# EBN_Storage_V01.net
KiCad netlist of a schematic drawn in EAGLE
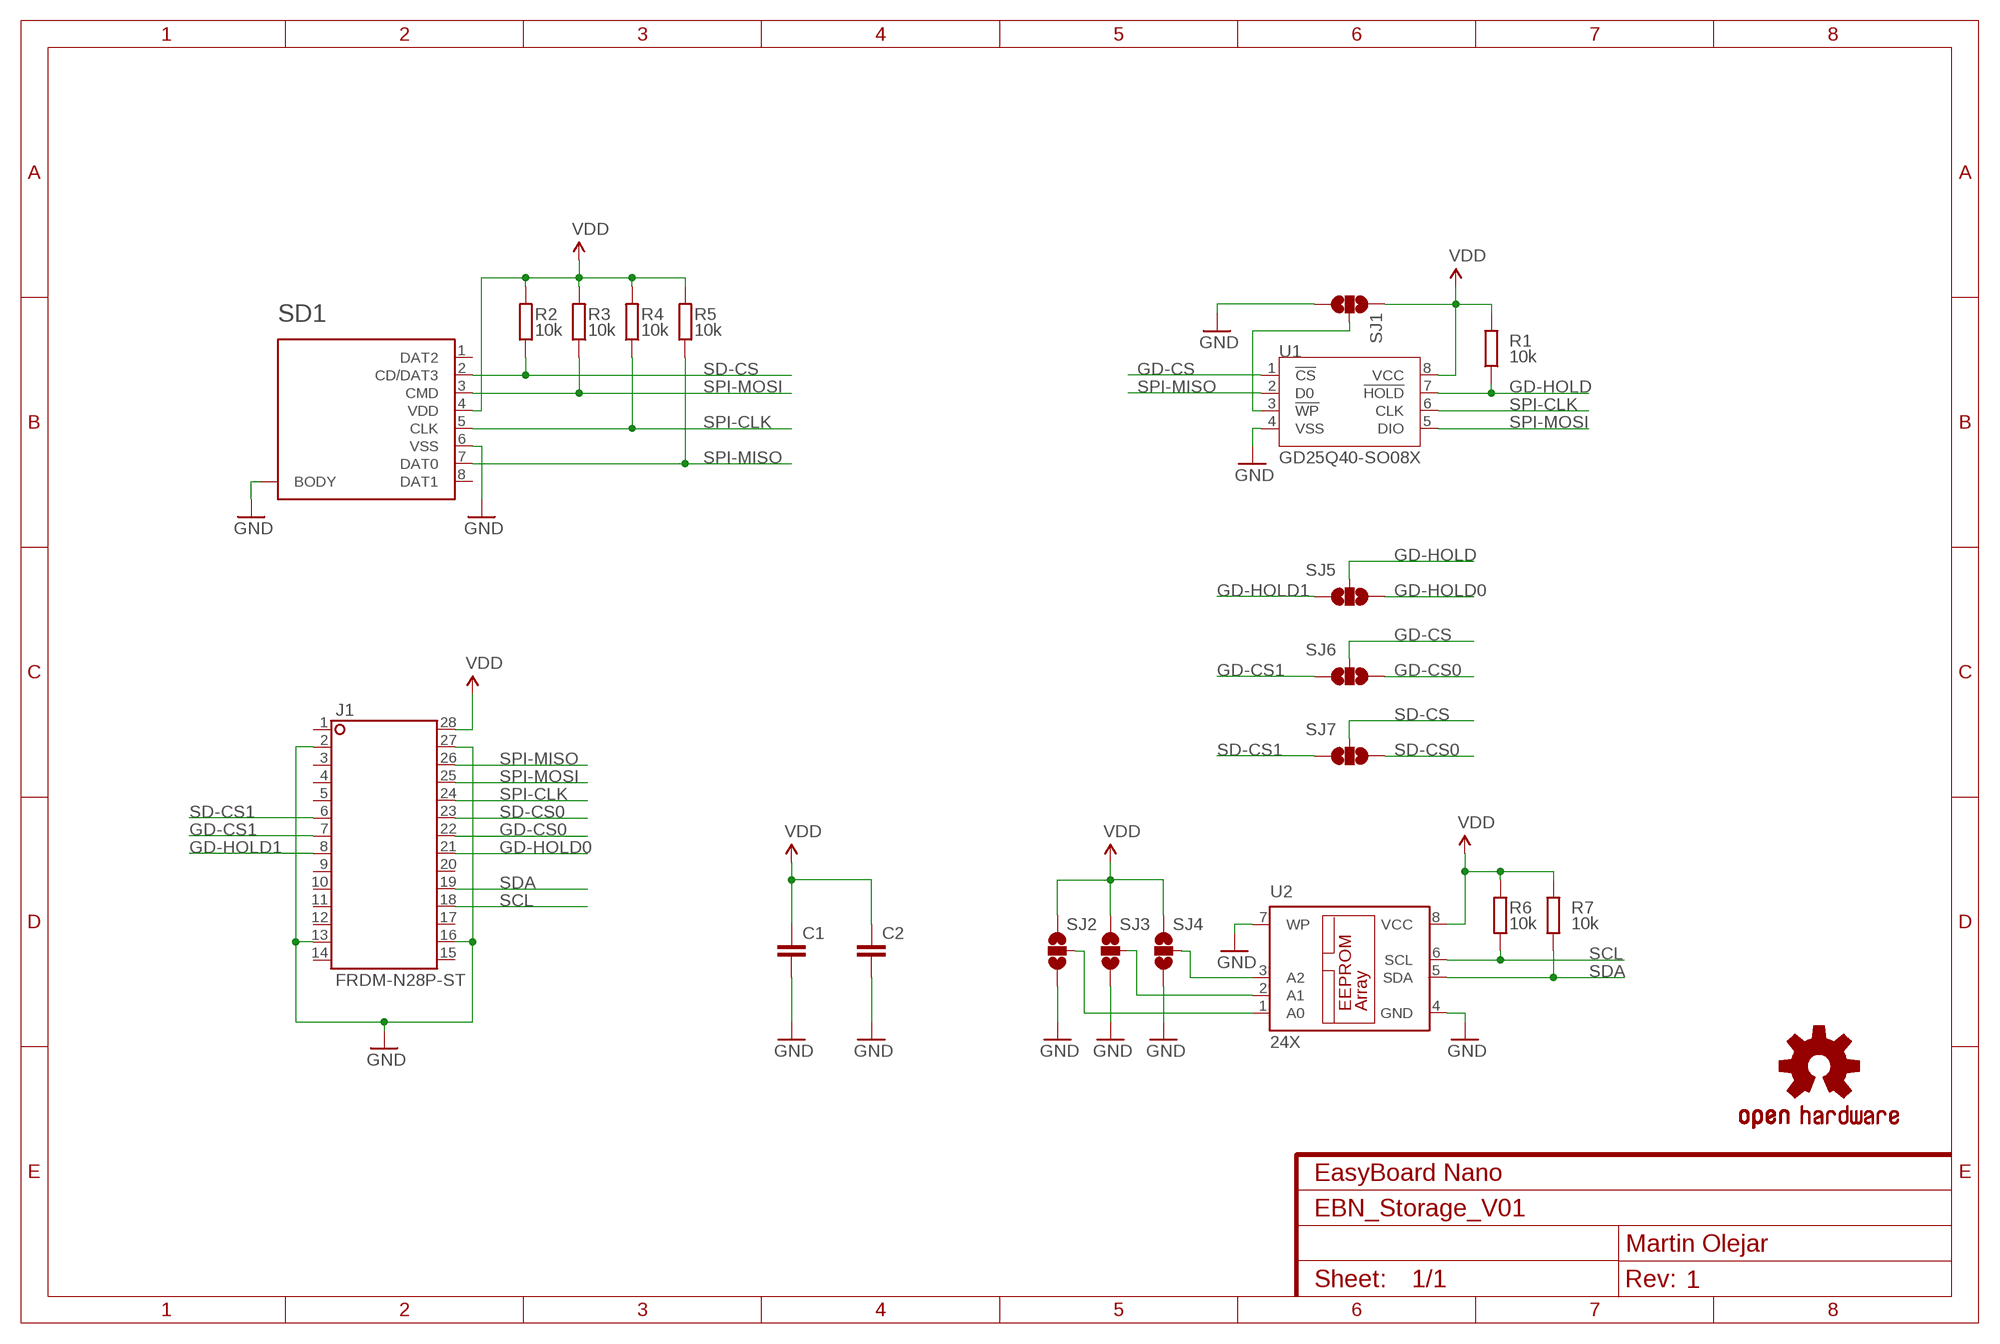
[diagram p0: schematic, sheet 1]

(export (version "E")
  (design (tool "Eeschema 10.0.6"))
  (components
    (comp (ref "C1")
      (value "C-EUC0402")
      (footprint "eagle-import:C0402")
      (libsource (lib "eagle-import") (part "C-EUC0402"))
    )
    (comp (ref "C2")
      (value "C-EUC0603")
      (footprint "eagle-import:C0603")
      (libsource (lib "eagle-import") (part "C-EUC0603"))
    )
    (comp (ref "J1")
      (value "FRDM-N28P-ST")
      (footprint "eagle-import:FRDM-N28P-SHIELD")
      (libsource (lib "eagle-import") (part "FRDM-N28P-ST"))
    )
    (comp (ref "LOGO1")
      (value "OSHW-LOGOM")
      (footprint "eagle-import:OSHW-LOGO-M")
      (libsource (lib "eagle-import") (part "OSHW-LOGOM"))
    )
    (comp (ref "R1")
      (value "10k")
      (footprint "eagle-import:R0603")
      (libsource (lib "eagle-import") (part "R-EUR0603"))
    )
    (comp (ref "R2")
      (value "10k")
      (footprint "eagle-import:R0402")
      (libsource (lib "eagle-import") (part "R-EUR0402"))
    )
    (comp (ref "R3")
      (value "10k")
      (footprint "eagle-import:R0402")
      (libsource (lib "eagle-import") (part "R-EUR0402"))
    )
    (comp (ref "R4")
      (value "10k")
      (footprint "eagle-import:R0402")
      (libsource (lib "eagle-import") (part "R-EUR0402"))
    )
    (comp (ref "R5")
      (value "10k")
      (footprint "eagle-import:R0402")
      (libsource (lib "eagle-import") (part "R-EUR0402"))
    )
    (comp (ref "R6")
      (value "10k")
      (footprint "eagle-import:R0603")
      (libsource (lib "eagle-import") (part "R-EUR0603"))
    )
    (comp (ref "R7")
      (value "10k")
      (footprint "eagle-import:R0603")
      (libsource (lib "eagle-import") (part "R-EUR0603"))
    )
    (comp (ref "SD1")
      (value "SDCARD")
      (footprint "eagle-import:MICRO-SD-01")
      (libsource (lib "eagle-import") (part "SDCARD"))
    )
    (comp (ref "SJ1")
      (value "SJ2W-S")
      (footprint "eagle-import:JUMPER-SMD-S2X")
      (libsource (lib "eagle-import") (part "SJ2W-S"))
    )
    (comp (ref "SJ2")
      (value "SJ2W-S")
      (footprint "eagle-import:JUMPER-SMD-S2X")
      (libsource (lib "eagle-import") (part "SJ2W-S"))
    )
    (comp (ref "SJ3")
      (value "SJ2W-S")
      (footprint "eagle-import:JUMPER-SMD-S2X")
      (libsource (lib "eagle-import") (part "SJ2W-S"))
    )
    (comp (ref "SJ4")
      (value "SJ2W-S")
      (footprint "eagle-import:JUMPER-SMD-S2X")
      (libsource (lib "eagle-import") (part "SJ2W-S"))
    )
    (comp (ref "SJ5")
      (value "SJ2W-S")
      (footprint "eagle-import:JUMPER-SMD-S2X")
      (libsource (lib "eagle-import") (part "SJ2W-S"))
    )
    (comp (ref "SJ6")
      (value "SJ2W-S")
      (footprint "eagle-import:JUMPER-SMD-S2X")
      (libsource (lib "eagle-import") (part "SJ2W-S"))
    )
    (comp (ref "SJ7")
      (value "SJ2W-S")
      (footprint "eagle-import:JUMPER-SMD-S2X")
      (libsource (lib "eagle-import") (part "SJ2W-S"))
    )
    (comp (ref "U1")
      (value "GD25Q40-SO08X")
      (footprint "eagle-import:SO08X@1")
      (libsource (lib "eagle-import") (part "GD25Q40-SO08X"))
    )
    (comp (ref "U2")
      (value "24X")
      (footprint "eagle-import:SO08X")
      (libsource (lib "eagle-import") (part "24X"))
    )
  )
  (nets
    (net (code "1") (name "/GD-CS") (class "Default")
      (node (ref "SJ6") (pin "2") (pinfunction "2_2") (pintype "passive"))
      (node (ref "U1") (pin "1") (pinfunction "~{CS}_1") (pintype "input"))
    )
    (net (code "2") (name "/GD-CS0") (class "Default")
      (node (ref "J1") (pin "22") (pinfunction "22_22") (pintype "passive"))
      (node (ref "SJ6") (pin "1") (pinfunction "1_1") (pintype "passive"))
    )
    (net (code "3") (name "/GD-CS1") (class "Default")
      (node (ref "J1") (pin "7") (pinfunction "7_7") (pintype "passive"))
      (node (ref "SJ6") (pin "3") (pinfunction "3_3") (pintype "passive"))
    )
    (net (code "4") (name "/GD-HOLD") (class "Default")
      (node (ref "R1") (pin "1") (pinfunction "1_1") (pintype "passive"))
      (node (ref "SJ5") (pin "2") (pinfunction "2_2") (pintype "passive"))
      (node (ref "U1") (pin "7") (pinfunction "~{HOLD}_7") (pintype "input"))
    )
    (net (code "5") (name "/GD-HOLD0") (class "Default")
      (node (ref "J1") (pin "21") (pinfunction "21_21") (pintype "passive"))
      (node (ref "SJ5") (pin "1") (pinfunction "1_1") (pintype "passive"))
    )
    (net (code "6") (name "/GD-HOLD1") (class "Default")
      (node (ref "J1") (pin "8") (pinfunction "8_8") (pintype "passive"))
      (node (ref "SJ5") (pin "3") (pinfunction "3_3") (pintype "passive"))
    )
    (net (code "7") (name "/SCL") (class "Default")
      (node (ref "J1") (pin "18") (pinfunction "18_18") (pintype "passive"))
      (node (ref "R6") (pin "1") (pinfunction "1_1") (pintype "passive"))
      (node (ref "U2") (pin "6") (pinfunction "SCL_6") (pintype "input"))
    )
    (net (code "8") (name "/SD-CS") (class "Default")
      (node (ref "R2") (pin "1") (pinfunction "1_1") (pintype "passive"))
      (node (ref "SD1") (pin "2") (pinfunction "CD/DAT3_2") (pintype "bidirectional"))
      (node (ref "SJ7") (pin "2") (pinfunction "2_2") (pintype "passive"))
    )
    (net (code "9") (name "/SD-CS0") (class "Default")
      (node (ref "J1") (pin "23") (pinfunction "23_23") (pintype "passive"))
      (node (ref "SJ7") (pin "1") (pinfunction "1_1") (pintype "passive"))
    )
    (net (code "10") (name "/SD-CS1") (class "Default")
      (node (ref "J1") (pin "6") (pinfunction "6_6") (pintype "passive"))
      (node (ref "SJ7") (pin "3") (pinfunction "3_3") (pintype "passive"))
    )
    (net (code "11") (name "/SDA") (class "Default")
      (node (ref "J1") (pin "19") (pinfunction "19_19") (pintype "passive"))
      (node (ref "R7") (pin "1") (pinfunction "1_1") (pintype "passive"))
      (node (ref "U2") (pin "5") (pinfunction "SDA_5") (pintype "bidirectional"))
    )
    (net (code "12") (name "/SPI-CLK") (class "Default")
      (node (ref "J1") (pin "24") (pinfunction "24_24") (pintype "passive"))
      (node (ref "R4") (pin "1") (pinfunction "1_1") (pintype "passive"))
      (node (ref "SD1") (pin "5") (pinfunction "CLK_5") (pintype "bidirectional"))
      (node (ref "U1") (pin "6") (pinfunction "CLK_6") (pintype "input"))
    )
    (net (code "13") (name "/SPI-MISO") (class "Default")
      (node (ref "J1") (pin "26") (pinfunction "26_26") (pintype "passive"))
      (node (ref "R5") (pin "1") (pinfunction "1_1") (pintype "passive"))
      (node (ref "SD1") (pin "7") (pinfunction "DAT0_7") (pintype "bidirectional"))
      (node (ref "U1") (pin "2") (pinfunction "D0_2") (pintype "output"))
    )
    (net (code "14") (name "/SPI-MOSI") (class "Default")
      (node (ref "J1") (pin "25") (pinfunction "25_25") (pintype "passive"))
      (node (ref "R3") (pin "1") (pinfunction "1_1") (pintype "passive"))
      (node (ref "SD1") (pin "3") (pinfunction "CMD_3") (pintype "bidirectional"))
      (node (ref "U1") (pin "5") (pinfunction "DIO_5") (pintype "bidirectional"))
    )
    (net (code "15") (name "GND") (class "Default")
      (node (ref "C1") (pin "2") (pinfunction "2_2") (pintype "passive"))
      (node (ref "C2") (pin "2") (pinfunction "2_2") (pintype "passive"))
      (node (ref "J1") (pin "13") (pinfunction "13_13") (pintype "passive"))
      (node (ref "J1") (pin "16") (pinfunction "16_16") (pintype "passive"))
      (node (ref "J1") (pin "2") (pinfunction "2_2") (pintype "passive"))
      (node (ref "J1") (pin "27") (pinfunction "27_27") (pintype "passive"))
      (node (ref "SD1") (pin "6") (pinfunction "VSS_6") (pintype "power_in"))
      (node (ref "SD1") (pin "SHELD@0") (pinfunction "BODY_SHELD@0") (pintype "passive"))
      (node (ref "SD1") (pin "SHELD@1") (pinfunction "BODY_SHELD@1") (pintype "passive"))
      (node (ref "SJ1") (pin "1") (pinfunction "1_1") (pintype "passive"))
      (node (ref "SJ2") (pin "1") (pinfunction "1_1") (pintype "passive"))
      (node (ref "SJ3") (pin "1") (pinfunction "1_1") (pintype "passive"))
      (node (ref "SJ4") (pin "1") (pinfunction "1_1") (pintype "passive"))
      (node (ref "U1") (pin "4") (pinfunction "VSS_4") (pintype "power_in"))
      (node (ref "U2") (pin "4") (pinfunction "GND_4") (pintype "power_in"))
      (node (ref "U2") (pin "7") (pinfunction "WP_7") (pintype "input"))
    )
    (net (code "16") (name "Net-(U1-~{WP})") (class "Default")
      (node (ref "SJ1") (pin "2") (pinfunction "2_2") (pintype "passive"))
      (node (ref "U1") (pin "3") (pinfunction "~{WP}_3") (pintype "input"))
    )
    (net (code "17") (name "Net-(U2-A0)") (class "Default")
      (node (ref "SJ2") (pin "2") (pinfunction "2_2") (pintype "passive"))
      (node (ref "U2") (pin "1") (pinfunction "A0_1") (pintype "input"))
    )
    (net (code "18") (name "Net-(U2-A1)") (class "Default")
      (node (ref "SJ3") (pin "2") (pinfunction "2_2") (pintype "passive"))
      (node (ref "U2") (pin "2") (pinfunction "A1_2") (pintype "input"))
    )
    (net (code "19") (name "Net-(U2-A2)") (class "Default")
      (node (ref "SJ4") (pin "2") (pinfunction "2_2") (pintype "passive"))
      (node (ref "U2") (pin "3") (pinfunction "A2_3") (pintype "input"))
    )
    (net (code "20") (name "VDD") (class "Default")
      (node (ref "C1") (pin "1") (pinfunction "1_1") (pintype "passive"))
      (node (ref "C2") (pin "1") (pinfunction "1_1") (pintype "passive"))
      (node (ref "J1") (pin "28") (pinfunction "28_28") (pintype "passive"))
      (node (ref "R1") (pin "2") (pinfunction "2_2") (pintype "passive"))
      (node (ref "R2") (pin "2") (pinfunction "2_2") (pintype "passive"))
      (node (ref "R3") (pin "2") (pinfunction "2_2") (pintype "passive"))
      (node (ref "R4") (pin "2") (pinfunction "2_2") (pintype "passive"))
      (node (ref "R5") (pin "2") (pinfunction "2_2") (pintype "passive"))
      (node (ref "R6") (pin "2") (pinfunction "2_2") (pintype "passive"))
      (node (ref "R7") (pin "2") (pinfunction "2_2") (pintype "passive"))
      (node (ref "SD1") (pin "4") (pinfunction "VDD_4") (pintype "power_in"))
      (node (ref "SJ1") (pin "3") (pinfunction "3_3") (pintype "passive"))
      (node (ref "SJ2") (pin "3") (pinfunction "3_3") (pintype "passive"))
      (node (ref "SJ3") (pin "3") (pinfunction "3_3") (pintype "passive"))
      (node (ref "SJ4") (pin "3") (pinfunction "3_3") (pintype "passive"))
      (node (ref "U1") (pin "8") (pinfunction "VCC_8") (pintype "power_in"))
      (node (ref "U2") (pin "8") (pinfunction "VCC_8") (pintype "power_in"))
    )
    (net (code "21") (name "unconnected-(J1-Pad1)") (class "Default")
      (node (ref "J1") (pin "1") (pinfunction "1_1") (pintype "passive"))
    )
    (net (code "22") (name "unconnected-(J1-Pad3)") (class "Default")
      (node (ref "J1") (pin "3") (pinfunction "3_3") (pintype "passive"))
    )
    (net (code "23") (name "unconnected-(J1-Pad4)") (class "Default")
      (node (ref "J1") (pin "4") (pinfunction "4_4") (pintype "passive"))
    )
    (net (code "24") (name "unconnected-(J1-Pad5)") (class "Default")
      (node (ref "J1") (pin "5") (pinfunction "5_5") (pintype "passive"))
    )
    (net (code "25") (name "unconnected-(J1-Pad9)") (class "Default")
      (node (ref "J1") (pin "9") (pinfunction "9_9") (pintype "passive"))
    )
    (net (code "26") (name "unconnected-(J1-Pad10)") (class "Default")
      (node (ref "J1") (pin "10") (pinfunction "10_10") (pintype "passive"))
    )
    (net (code "27") (name "unconnected-(J1-Pad11)") (class "Default")
      (node (ref "J1") (pin "11") (pinfunction "11_11") (pintype "passive"))
    )
    (net (code "28") (name "unconnected-(J1-Pad12)") (class "Default")
      (node (ref "J1") (pin "12") (pinfunction "12_12") (pintype "passive"))
    )
    (net (code "29") (name "unconnected-(J1-Pad14)") (class "Default")
      (node (ref "J1") (pin "14") (pinfunction "14_14") (pintype "passive"))
    )
    (net (code "30") (name "unconnected-(J1-Pad15)") (class "Default")
      (node (ref "J1") (pin "15") (pinfunction "15_15") (pintype "passive"))
    )
    (net (code "31") (name "unconnected-(J1-Pad17)") (class "Default")
      (node (ref "J1") (pin "17") (pinfunction "17_17") (pintype "passive"))
    )
    (net (code "32") (name "unconnected-(J1-Pad20)") (class "Default")
      (node (ref "J1") (pin "20") (pinfunction "20_20") (pintype "passive"))
    )
    (net (code "33") (name "unconnected-(SD1-DAT1-Pad8)") (class "Default")
      (node (ref "SD1") (pin "8") (pinfunction "DAT1_8") (pintype "bidirectional"))
    )
    (net (code "34") (name "unconnected-(SD1-DAT2-Pad1)") (class "Default")
      (node (ref "SD1") (pin "1") (pinfunction "DAT2_1") (pintype "bidirectional"))
    )
  )
)
